# ld100v1.net
KiCad netlist of a schematic drawn in EAGLE
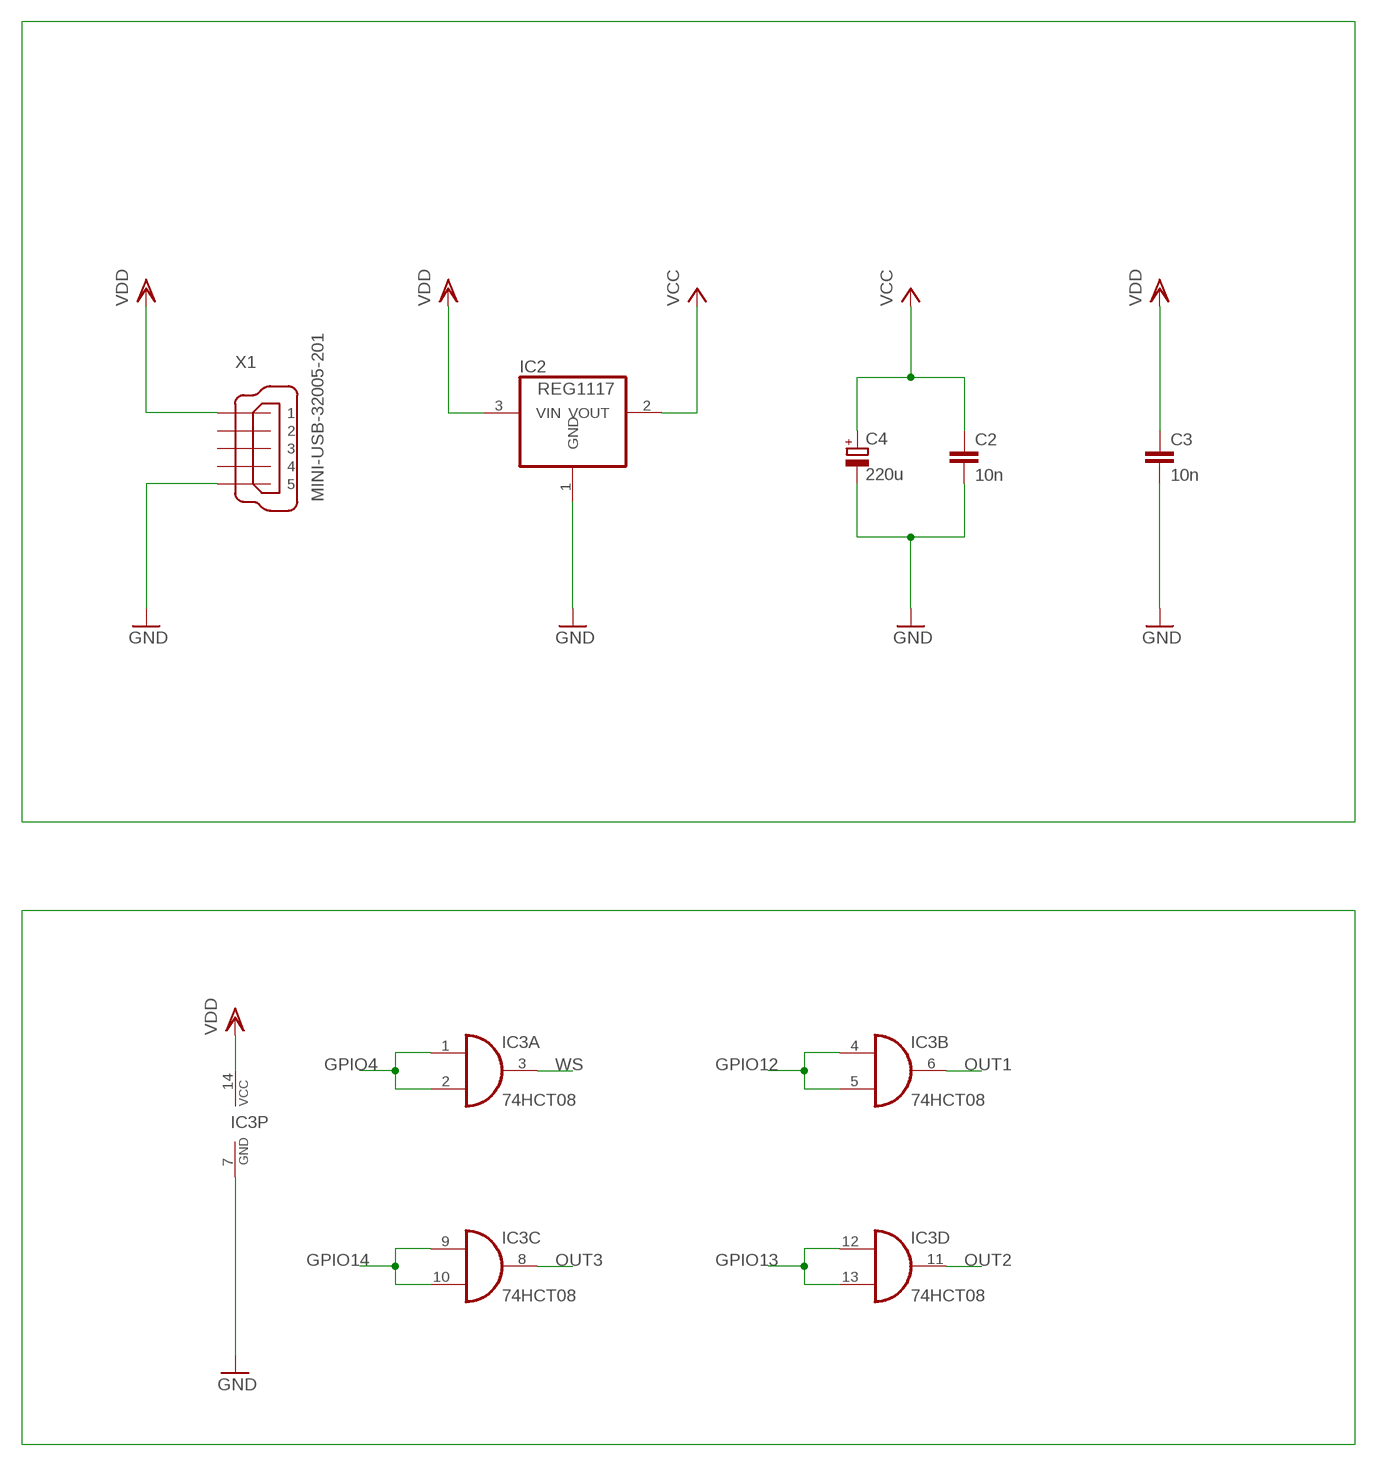
[diagram p0: schematic, sheet 1, part 1 of 2]
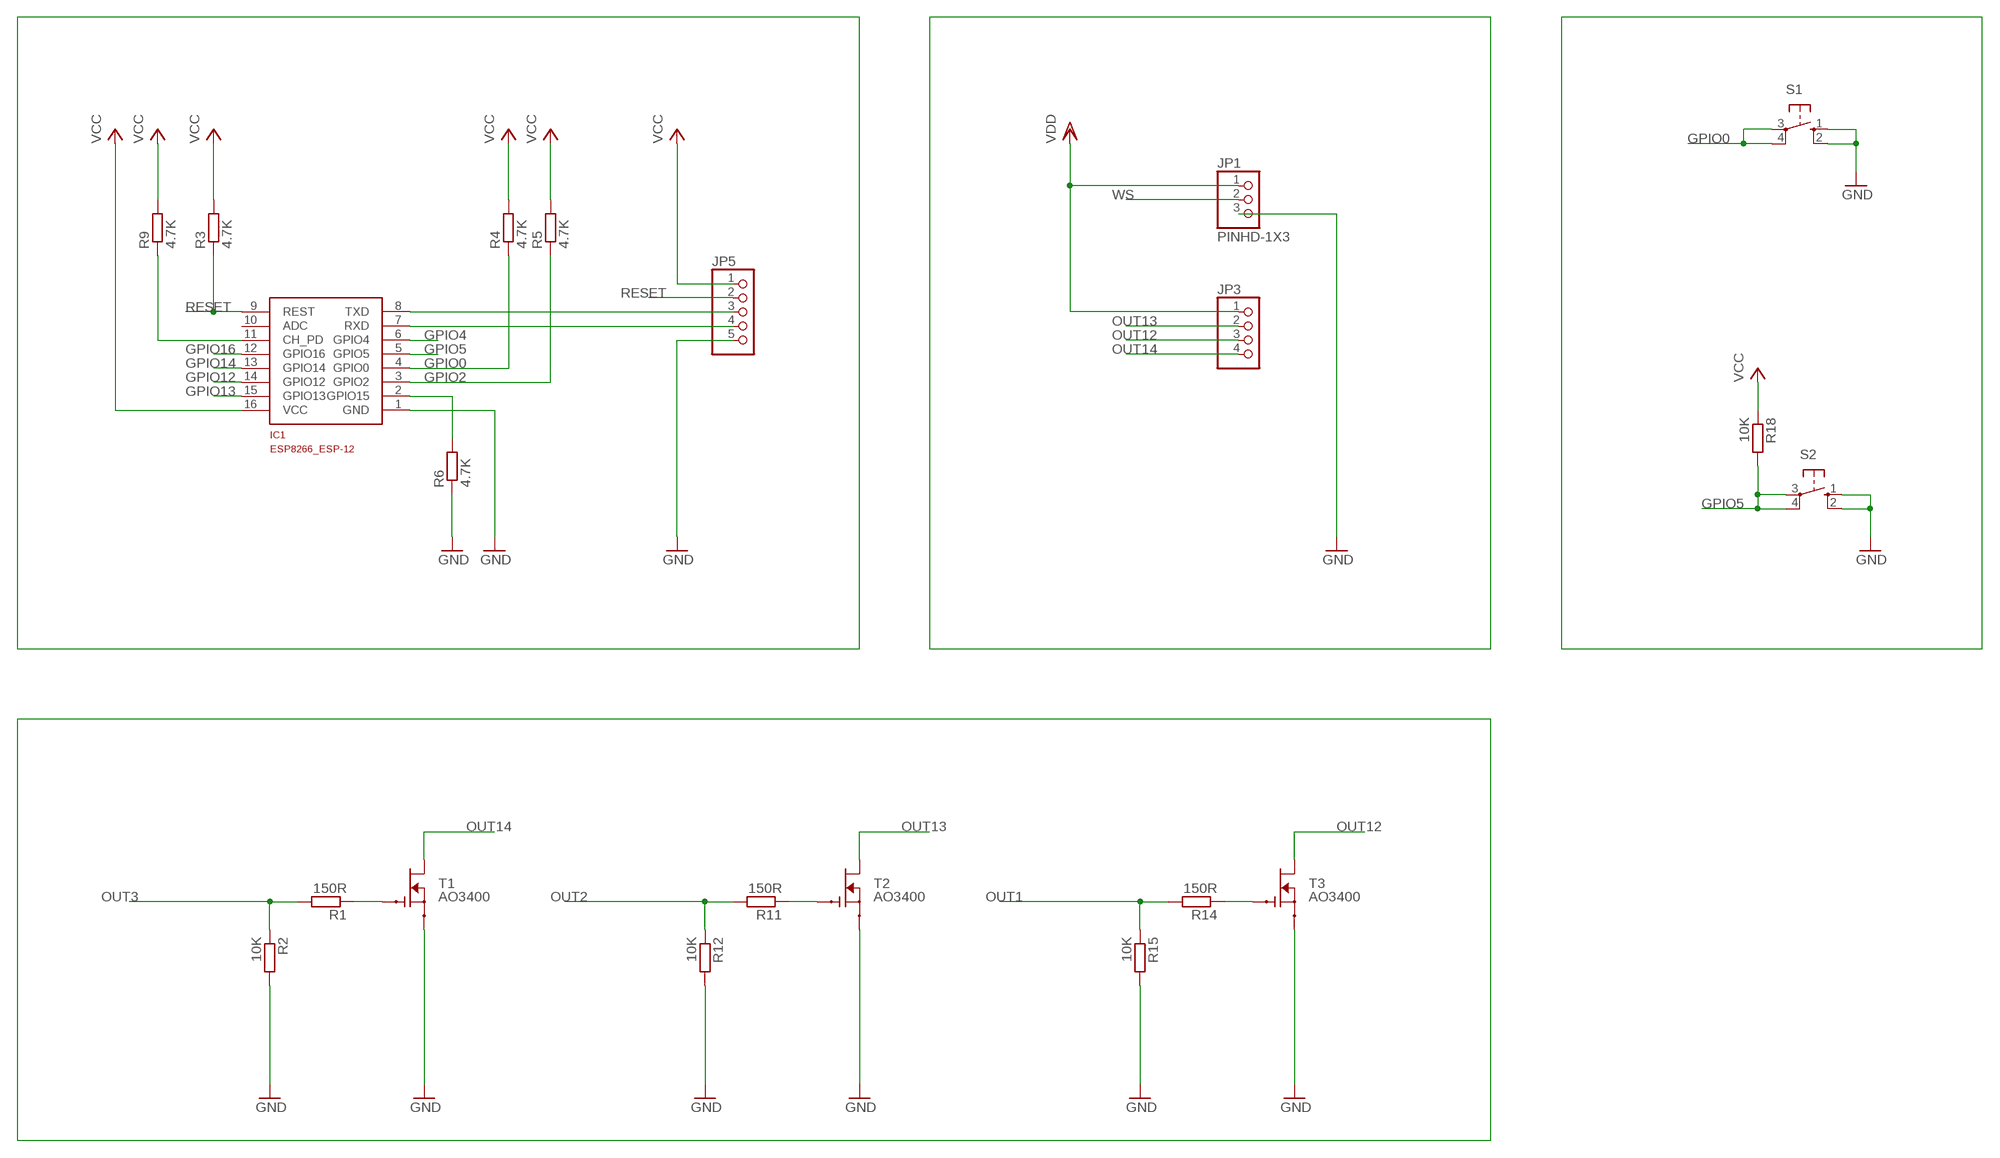
[diagram p1: schematic, sheet 1, part 2 of 2]

(export (version "E")
  (design (tool "Eeschema 10.0.6"))
  (components
    (comp (ref "C2")
      (value "10n")
      (footprint "eagle-import:C1206")
      (libsource (lib "eagle-import") (part "C-EUC1206"))
    )
    (comp (ref "C3")
      (value "10n")
      (footprint "eagle-import:C1206")
      (libsource (lib "eagle-import") (part "C-EUC1206"))
    )
    (comp (ref "C4")
      (value "220u")
      (footprint "eagle-import:UD-6,3X5,8_NICHICON")
      (libsource (lib "eagle-import") (part "CPOL-EUUD-6,3X8,8"))
    )
    (comp (ref "IC1")
      (value "ESP8266_ESP-12")
      (footprint "eagle-import:ESP8266-ESP12")
      (libsource (lib "eagle-import") (part "ESP8266_ESP-12"))
    )
    (comp (ref "IC2")
      (value "REG1117")
      (footprint "eagle-import:SOT223")
      (libsource (lib "eagle-import") (part "REG1117"))
    )
    (comp (ref "IC3")
      (value "74HCT08")
      (footprint "eagle-import:SO14")
      (libsource (lib "eagle-import") (part "7408DAC"))
    )
    (comp (ref "JP1")
      (value "PINHD-1X3")
      (footprint "eagle-import:1X03")
      (libsource (lib "eagle-import") (part "PINHD-1X3"))
    )
    (comp (ref "JP3")
      (value "PINHD-1X4")
      (footprint "eagle-import:1X04")
      (libsource (lib "eagle-import") (part "PINHD-1X4"))
    )
    (comp (ref "JP5")
      (value "PINHD-1X5")
      (footprint "eagle-import:1X05")
      (libsource (lib "eagle-import") (part "PINHD-1X5"))
    )
    (comp (ref "R1")
      (value "150R")
      (footprint "eagle-import:R1206")
      (libsource (lib "eagle-import") (part "R-EU_R1206"))
    )
    (comp (ref "R2")
      (value "10K")
      (footprint "eagle-import:R1206")
      (libsource (lib "eagle-import") (part "R-EU_R1206"))
    )
    (comp (ref "R3")
      (value "4.7K")
      (footprint "eagle-import:R1206")
      (libsource (lib "eagle-import") (part "R-EU_R1206"))
    )
    (comp (ref "R4")
      (value "4.7K")
      (footprint "eagle-import:R1206")
      (libsource (lib "eagle-import") (part "R-EU_R1206"))
    )
    (comp (ref "R5")
      (value "4.7K")
      (footprint "eagle-import:R1206")
      (libsource (lib "eagle-import") (part "R-EU_R1206"))
    )
    (comp (ref "R6")
      (value "4.7K")
      (footprint "eagle-import:R1206")
      (libsource (lib "eagle-import") (part "R-EU_R1206"))
    )
    (comp (ref "R9")
      (value "4.7K")
      (footprint "eagle-import:R1206")
      (libsource (lib "eagle-import") (part "R-EU_R1206"))
    )
    (comp (ref "R11")
      (value "150R")
      (footprint "eagle-import:R1206")
      (libsource (lib "eagle-import") (part "R-EU_R1206"))
    )
    (comp (ref "R12")
      (value "10K")
      (footprint "eagle-import:R1206")
      (libsource (lib "eagle-import") (part "R-EU_R1206"))
    )
    (comp (ref "R14")
      (value "150R")
      (footprint "eagle-import:R1206")
      (libsource (lib "eagle-import") (part "R-EU_R1206"))
    )
    (comp (ref "R15")
      (value "10K")
      (footprint "eagle-import:R1206")
      (libsource (lib "eagle-import") (part "R-EU_R1206"))
    )
    (comp (ref "R18")
      (value "10K")
      (footprint "eagle-import:R1206")
      (libsource (lib "eagle-import") (part "R-EU_R1206"))
    )
    (comp (ref "S1")
      (value "10-XX")
      (footprint "eagle-import:B3F-10XX")
      (fields (field (name "MPN") "B3F-1000"))
      (libsource (lib "eagle-import") (part "10-XX"))
    )
    (comp (ref "S2")
      (value "10-XX")
      (footprint "eagle-import:B3F-10XX")
      (fields (field (name "MPN") "B3F-1000"))
      (libsource (lib "eagle-import") (part "10-XX"))
    )
    (comp (ref "T1")
      (value "AO3400")
      (footprint "eagle-import:SOT23")
      (fields (field (name "MF") "Alpha &"))
      (libsource (lib "eagle-import") (part "AO3400"))
    )
    (comp (ref "T2")
      (value "AO3400")
      (footprint "eagle-import:SOT23")
      (fields (field (name "MF") "Alpha &"))
      (libsource (lib "eagle-import") (part "AO3400"))
    )
    (comp (ref "T3")
      (value "AO3400")
      (footprint "eagle-import:SOT23")
      (fields (field (name "MF") "Alpha &"))
      (libsource (lib "eagle-import") (part "AO3400"))
    )
    (comp (ref "X1")
      (value "MINI-USB-32005-201")
      (footprint "eagle-import:32005-201")
      (libsource (lib "eagle-import") (part "MINI-USB-32005-201"))
    )
  )
  (nets
    (net (code "1") (name "/GPIO0") (class "Default")
      (node (ref "IC1") (pin "4") (pinfunction "GPIO0_4") (pintype "bidirectional"))
      (node (ref "R4") (pin "1") (pinfunction "1_1") (pintype "passive"))
      (node (ref "S1") (pin "3") (pinfunction "P_3") (pintype "passive"))
      (node (ref "S1") (pin "4") (pinfunction "P1_4") (pintype "passive"))
    )
    (net (code "2") (name "/GPIO2") (class "Default")
      (node (ref "IC1") (pin "3") (pinfunction "GPIO2_3") (pintype "bidirectional"))
      (node (ref "R5") (pin "1") (pinfunction "1_1") (pintype "passive"))
    )
    (net (code "3") (name "/GPIO4") (class "Default")
      (node (ref "IC1") (pin "6") (pinfunction "GPIO4_6") (pintype "bidirectional"))
      (node (ref "IC3") (pin "1") (pinfunction "I0_1") (pintype "input"))
      (node (ref "IC3") (pin "2") (pinfunction "I1_2") (pintype "input"))
    )
    (net (code "4") (name "/GPIO5") (class "Default")
      (node (ref "IC1") (pin "5") (pinfunction "GPIO5_5") (pintype "bidirectional"))
      (node (ref "R18") (pin "2") (pinfunction "2_2") (pintype "passive"))
      (node (ref "S2") (pin "3") (pinfunction "P_3") (pintype "passive"))
      (node (ref "S2") (pin "4") (pinfunction "P1_4") (pintype "passive"))
    )
    (net (code "5") (name "/GPIO12") (class "Default")
      (node (ref "IC1") (pin "14") (pinfunction "GPIO12_14") (pintype "bidirectional"))
      (node (ref "IC3") (pin "4") (pinfunction "I0_4") (pintype "input"))
      (node (ref "IC3") (pin "5") (pinfunction "I1_5") (pintype "input"))
    )
    (net (code "6") (name "/GPIO13") (class "Default")
      (node (ref "IC1") (pin "15") (pinfunction "GPIO13_15") (pintype "bidirectional"))
      (node (ref "IC3") (pin "12") (pinfunction "I0_12") (pintype "input"))
      (node (ref "IC3") (pin "13") (pinfunction "I1_13") (pintype "input"))
    )
    (net (code "7") (name "/GPIO14") (class "Default")
      (node (ref "IC1") (pin "13") (pinfunction "GPIO14_13") (pintype "bidirectional"))
      (node (ref "IC3") (pin "10") (pinfunction "I1_10") (pintype "input"))
      (node (ref "IC3") (pin "9") (pinfunction "I0_9") (pintype "input"))
    )
    (net (code "8") (name "/GPIO16") (class "Default")
      (node (ref "IC1") (pin "12") (pinfunction "GPIO16_12") (pintype "bidirectional"))
    )
    (net (code "9") (name "/OUT1") (class "Default")
      (node (ref "IC3") (pin "6") (pinfunction "O_6") (pintype "output"))
      (node (ref "R14") (pin "2") (pinfunction "2_2") (pintype "passive"))
      (node (ref "R15") (pin "1") (pinfunction "1_1") (pintype "passive"))
    )
    (net (code "10") (name "/OUT2") (class "Default")
      (node (ref "IC3") (pin "11") (pinfunction "O_11") (pintype "output"))
      (node (ref "R11") (pin "2") (pinfunction "2_2") (pintype "passive"))
      (node (ref "R12") (pin "1") (pinfunction "1_1") (pintype "passive"))
    )
    (net (code "11") (name "/OUT3") (class "Default")
      (node (ref "IC3") (pin "8") (pinfunction "O_8") (pintype "output"))
      (node (ref "R1") (pin "2") (pinfunction "2_2") (pintype "passive"))
      (node (ref "R2") (pin "1") (pinfunction "1_1") (pintype "passive"))
    )
    (net (code "12") (name "/OUT12") (class "Default")
      (node (ref "JP3") (pin "3") (pinfunction "3_3") (pintype "passive"))
      (node (ref "T3") (pin "3") (pinfunction "D_3") (pintype "passive"))
    )
    (net (code "13") (name "/OUT13") (class "Default")
      (node (ref "JP3") (pin "2") (pinfunction "2_2") (pintype "passive"))
      (node (ref "T2") (pin "3") (pinfunction "D_3") (pintype "passive"))
    )
    (net (code "14") (name "/OUT14") (class "Default")
      (node (ref "JP3") (pin "4") (pinfunction "4_4") (pintype "passive"))
      (node (ref "T1") (pin "3") (pinfunction "D_3") (pintype "passive"))
    )
    (net (code "15") (name "/RESET") (class "Default")
      (node (ref "IC1") (pin "9") (pinfunction "REST_9") (pintype "bidirectional"))
      (node (ref "JP5") (pin "2") (pinfunction "2_2") (pintype "passive"))
      (node (ref "R3") (pin "1") (pinfunction "1_1") (pintype "passive"))
    )
    (net (code "16") (name "/WS") (class "Default")
      (node (ref "IC3") (pin "3") (pinfunction "O_3") (pintype "output"))
      (node (ref "JP1") (pin "2") (pinfunction "2_2") (pintype "passive"))
    )
    (net (code "17") (name "GND") (class "Default")
      (node (ref "C2") (pin "2") (pinfunction "2_2") (pintype "passive"))
      (node (ref "C3") (pin "2") (pinfunction "2_2") (pintype "passive"))
      (node (ref "C4") (pin "-") (pinfunction "-_-") (pintype "passive"))
      (node (ref "IC1") (pin "1") (pinfunction "GND_1") (pintype "bidirectional"))
      (node (ref "IC2") (pin "1") (pinfunction "GND_1") (pintype "power_in"))
      (node (ref "IC3") (pin "7") (pinfunction "GND_7") (pintype "power_in"))
      (node (ref "JP1") (pin "3") (pinfunction "3_3") (pintype "passive"))
      (node (ref "JP5") (pin "5") (pinfunction "5_5") (pintype "passive"))
      (node (ref "R12") (pin "2") (pinfunction "2_2") (pintype "passive"))
      (node (ref "R15") (pin "2") (pinfunction "2_2") (pintype "passive"))
      (node (ref "R2") (pin "2") (pinfunction "2_2") (pintype "passive"))
      (node (ref "R6") (pin "1") (pinfunction "1_1") (pintype "passive"))
      (node (ref "S1") (pin "1") (pinfunction "S_1") (pintype "passive"))
      (node (ref "S1") (pin "2") (pinfunction "S1_2") (pintype "passive"))
      (node (ref "S2") (pin "1") (pinfunction "S_1") (pintype "passive"))
      (node (ref "S2") (pin "2") (pinfunction "S1_2") (pintype "passive"))
      (node (ref "T1") (pin "2") (pinfunction "S_2") (pintype "passive"))
      (node (ref "T2") (pin "2") (pinfunction "S_2") (pintype "passive"))
      (node (ref "T3") (pin "2") (pinfunction "S_2") (pintype "passive"))
      (node (ref "X1") (pin "5") (pinfunction "5_5") (pintype "passive"))
    )
    (net (code "18") (name "Net-(IC1-CH_PD)") (class "Default")
      (node (ref "IC1") (pin "11") (pinfunction "CH_PD_11") (pintype "bidirectional"))
      (node (ref "R9") (pin "1") (pinfunction "1_1") (pintype "passive"))
    )
    (net (code "19") (name "Net-(IC1-GPIO15)") (class "Default")
      (node (ref "IC1") (pin "2") (pinfunction "GPIO15_2") (pintype "bidirectional"))
      (node (ref "R6") (pin "2") (pinfunction "2_2") (pintype "passive"))
    )
    (net (code "20") (name "Net-(IC1-RXD)") (class "Default")
      (node (ref "IC1") (pin "7") (pinfunction "RXD_7") (pintype "bidirectional"))
      (node (ref "JP5") (pin "4") (pinfunction "4_4") (pintype "passive"))
    )
    (net (code "21") (name "Net-(IC1-TXD)") (class "Default")
      (node (ref "IC1") (pin "8") (pinfunction "TXD_8") (pintype "bidirectional"))
      (node (ref "JP5") (pin "3") (pinfunction "3_3") (pintype "passive"))
    )
    (net (code "22") (name "Net-(T1-G)") (class "Default")
      (node (ref "R1") (pin "1") (pinfunction "1_1") (pintype "passive"))
      (node (ref "T1") (pin "1") (pinfunction "G_1") (pintype "passive"))
    )
    (net (code "23") (name "Net-(T2-G)") (class "Default")
      (node (ref "R11") (pin "1") (pinfunction "1_1") (pintype "passive"))
      (node (ref "T2") (pin "1") (pinfunction "G_1") (pintype "passive"))
    )
    (net (code "24") (name "Net-(T3-G)") (class "Default")
      (node (ref "R14") (pin "1") (pinfunction "1_1") (pintype "passive"))
      (node (ref "T3") (pin "1") (pinfunction "G_1") (pintype "passive"))
    )
    (net (code "25") (name "VCC") (class "Default")
      (node (ref "C2") (pin "1") (pinfunction "1_1") (pintype "passive"))
      (node (ref "C4") (pin "+") (pinfunction "+_+") (pintype "passive"))
      (node (ref "IC1") (pin "16") (pinfunction "VCC_16") (pintype "bidirectional"))
      (node (ref "IC2") (pin "2") (pinfunction "VOUT_2") (pintype "output"))
      (node (ref "JP5") (pin "1") (pinfunction "1_1") (pintype "passive"))
      (node (ref "R18") (pin "1") (pinfunction "1_1") (pintype "passive"))
      (node (ref "R3") (pin "2") (pinfunction "2_2") (pintype "passive"))
      (node (ref "R4") (pin "2") (pinfunction "2_2") (pintype "passive"))
      (node (ref "R5") (pin "2") (pinfunction "2_2") (pintype "passive"))
      (node (ref "R9") (pin "2") (pinfunction "2_2") (pintype "passive"))
    )
    (net (code "26") (name "VDD") (class "Default")
      (node (ref "C3") (pin "1") (pinfunction "1_1") (pintype "passive"))
      (node (ref "IC2") (pin "3") (pinfunction "VIN_3") (pintype "input"))
      (node (ref "IC3") (pin "14") (pinfunction "VCC_14") (pintype "power_in"))
      (node (ref "JP1") (pin "1") (pinfunction "1_1") (pintype "passive"))
      (node (ref "JP3") (pin "1") (pinfunction "1_1") (pintype "passive"))
      (node (ref "X1") (pin "1") (pinfunction "1_1") (pintype "passive"))
    )
    (net (code "27") (name "unconnected-(IC1-ADC-Pad10)") (class "Default")
      (node (ref "IC1") (pin "10") (pinfunction "ADC_10") (pintype "bidirectional"))
    )
    (net (code "28") (name "unconnected-(X1-Pad2)") (class "Default")
      (node (ref "X1") (pin "2") (pinfunction "2_2") (pintype "passive"))
    )
    (net (code "29") (name "unconnected-(X1-Pad3)") (class "Default")
      (node (ref "X1") (pin "3") (pinfunction "3_3") (pintype "passive"))
    )
    (net (code "30") (name "unconnected-(X1-Pad4)") (class "Default")
      (node (ref "X1") (pin "4") (pinfunction "4_4") (pintype "passive"))
    )
  )
)
